# lelay.net
KiCad netlist of a schematic drawn in Altium Designer
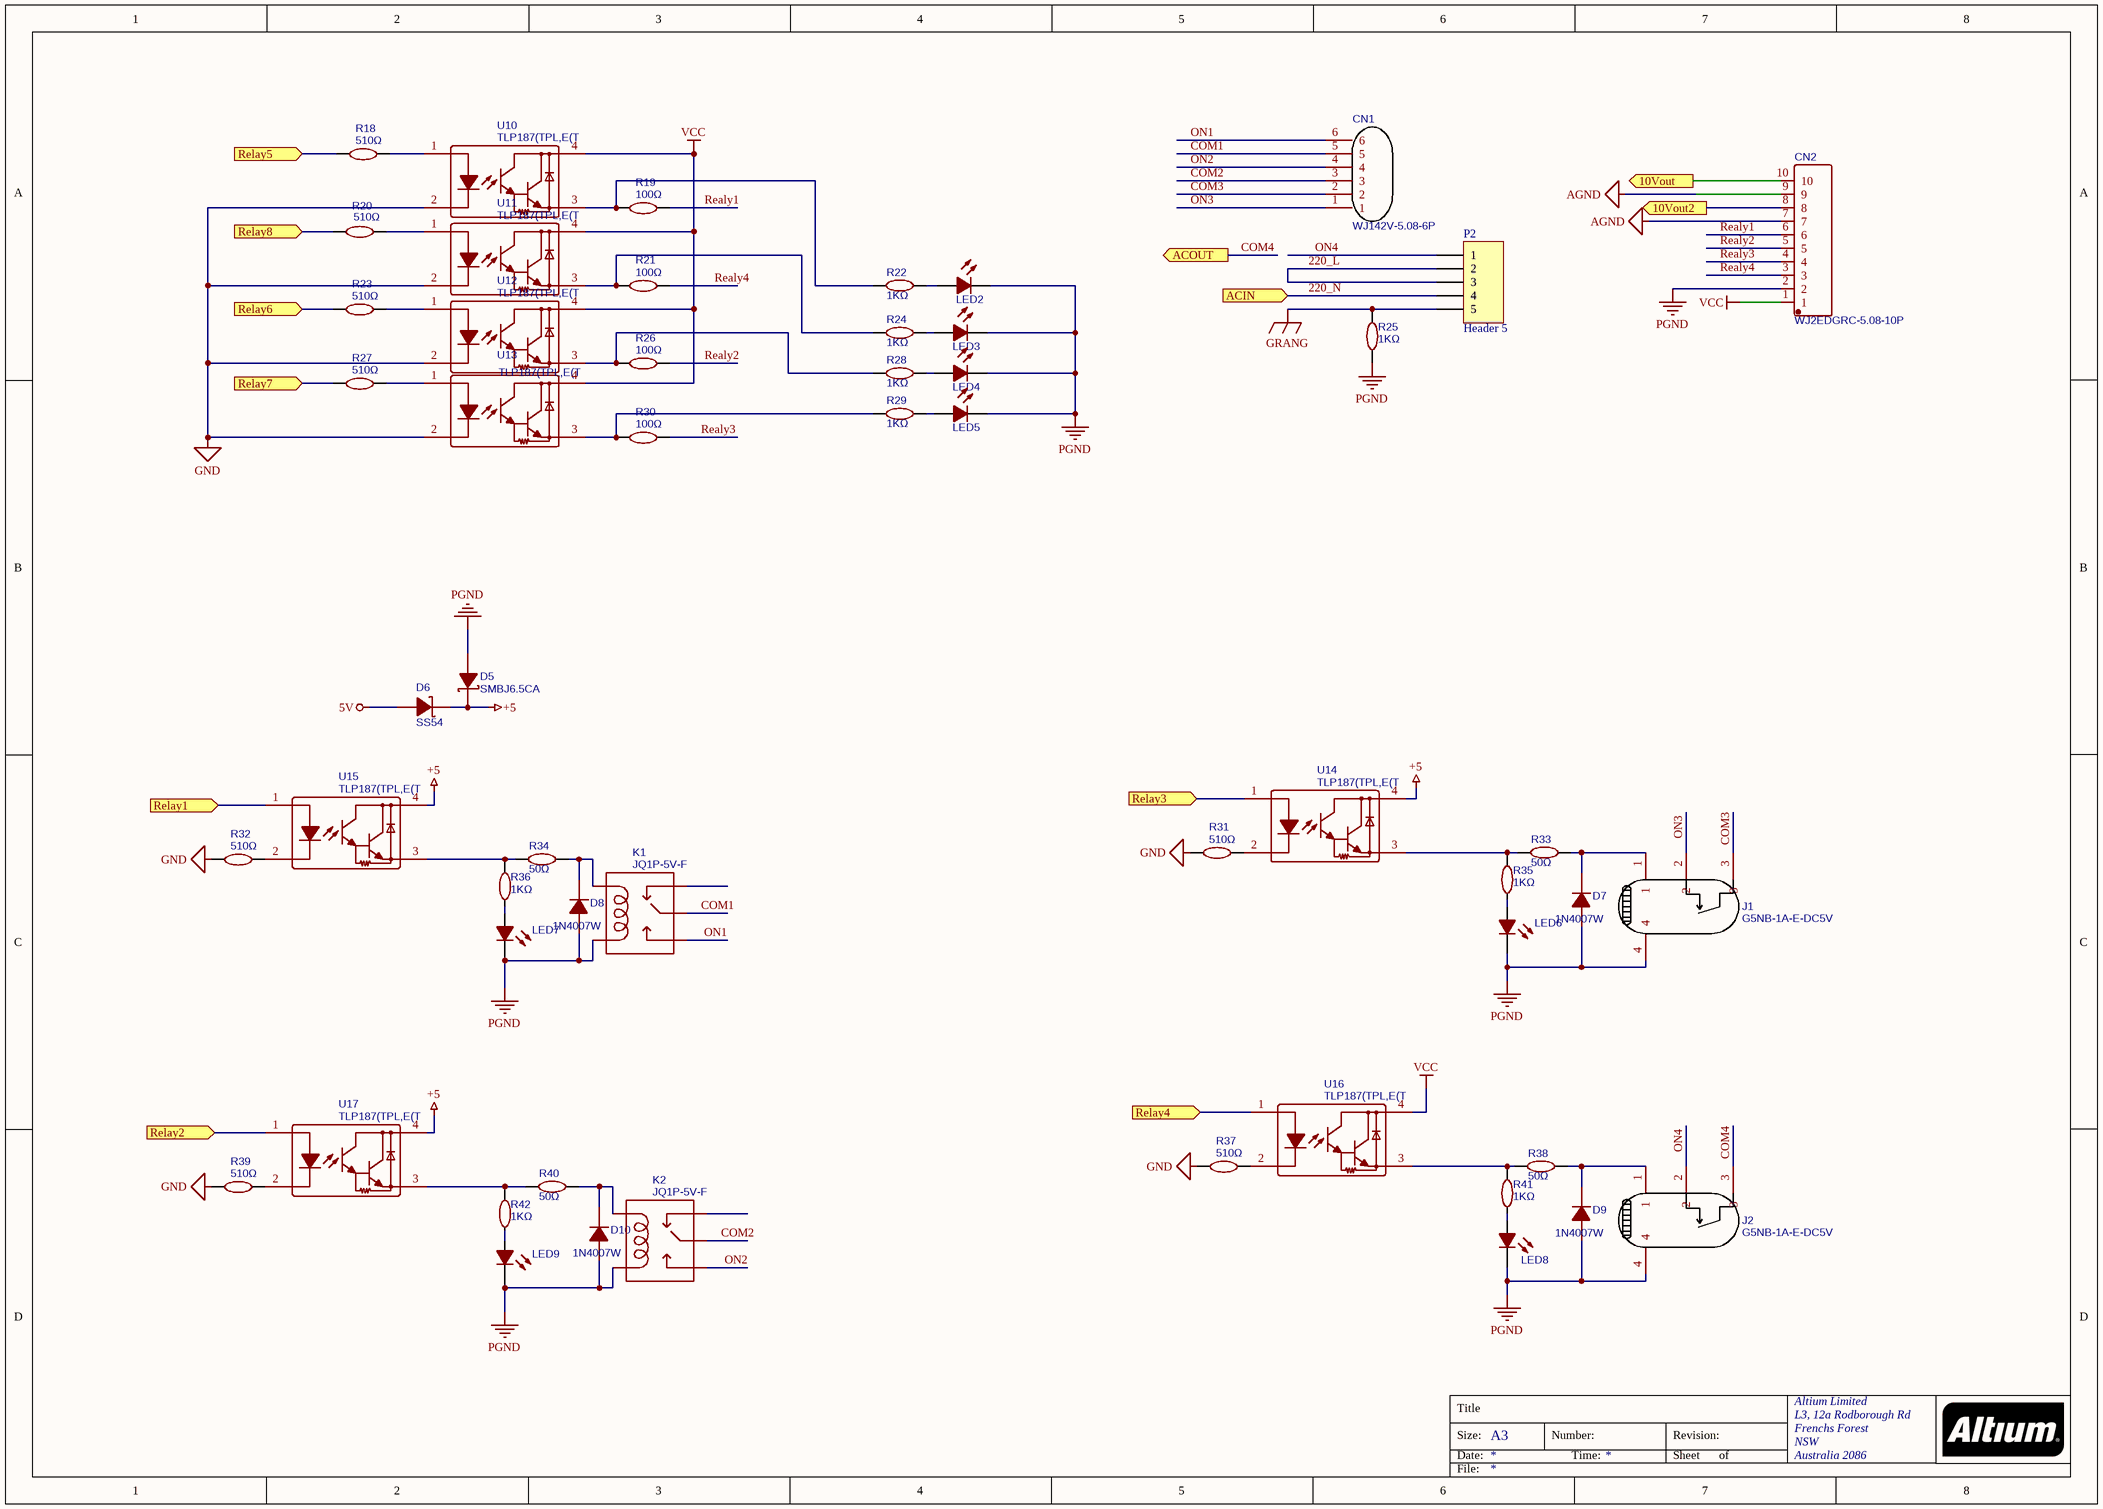
[diagram p0: lelay.SchDoc]

(export (version "E")
  (design (tool "Eeschema 10.0.6"))
  (components
    (comp (ref "CN1")
      (value "WJ142V-5.08-6P")
      (footprint "5.08_6P")
      (libsource (lib "altium-import") (part "root_1_mirrored__"))
    )
    (comp (ref "CN2")
      (value "WJ2EDGRC-5.08-10P")
      (footprint "WJ2EDGRC-5.08-10P")
      (libsource (lib "altium-import") (part "root_2_mirrored__"))
    )
    (comp (ref "D5")
      (value "SMBJ6.5CA")
      (footprint "SMB(DO-214AA)")
      (libsource (lib "altium-import") (part "root_1__"))
    )
    (comp (ref "D6") (value "SS54") (footprint "SMA(DO-214AC)") (libsource (lib "") (part "root_0___4")))
    (comp (ref "D7")
      (value "1N4007W")
      (footprint "SOD-123FL")
      (libsource (lib "altium-import") (part "root_3__"))
    )
    (comp (ref "D8")
      (value "1N4007W")
      (footprint "SOD-123FL")
      (libsource (lib "altium-import") (part "root_3__"))
    )
    (comp (ref "D9")
      (value "1N4007W")
      (footprint "SOD-123FL")
      (libsource (lib "altium-import") (part "root_3__"))
    )
    (comp (ref "D10")
      (value "1N4007W")
      (footprint "SOD-123FL")
      (libsource (lib "altium-import") (part "root_3__"))
    )
    (comp (ref "J1")
      (value "G5NB-1A-E-DC5V")
      (footprint "G5NB-1A-E-DC5V")
      (libsource (lib "") (part "root_0___6"))
    )
    (comp (ref "J2") (value "G5NB-1A-E-DC5V") (footprint "继电器") (libsource (lib "") (part "root_0___6")))
    (comp (ref "K1") (value "JQ1P-5V-F") (footprint "JQ1P-5V-F") (libsource (lib "") (part "root_0___5")))
    (comp (ref "K2") (value "JQ1P-5V-F") (footprint "JQ1P-5V-F") (libsource (lib "") (part "root_0___5")))
    (comp (ref "LED2")
      (value "19-217/GHC-YR1S2/3T")
      (footprint "LED-0603")
      (libsource (lib "altium-import") (part "root_0__"))
    )
    (comp (ref "LED3")
      (value "19-217/GHC-YR1S2/3T")
      (footprint "LED-0603")
      (libsource (lib "altium-import") (part "root_0__"))
    )
    (comp (ref "LED4")
      (value "19-217/GHC-YR1S2/3T")
      (footprint "LED-0603")
      (libsource (lib "altium-import") (part "root_0__"))
    )
    (comp (ref "LED5")
      (value "19-217/GHC-YR1S2/3T")
      (footprint "LED-0603")
      (libsource (lib "altium-import") (part "root_0__"))
    )
    (comp (ref "LED6")
      (value "19-217/GHC-YR1S2/3T")
      (footprint "LED-0603")
      (libsource (lib "") (part "root_3___2"))
    )
    (comp (ref "LED7")
      (value "19-217/GHC-YR1S2/3T")
      (footprint "LED-0603")
      (libsource (lib "") (part "root_3___2"))
    )
    (comp (ref "LED8")
      (value "19-217/GHC-YR1S2/3T")
      (footprint "LED-0603")
      (libsource (lib "") (part "root_3___2"))
    )
    (comp (ref "LED9")
      (value "19-217/GHC-YR1S2/3T")
      (footprint "LED-0603")
      (libsource (lib "") (part "root_3___2"))
    )
    (comp (ref "P2")
      (value "Header 5")
      (footprint "5p-7.62")
      (description "Header, 5-Pin")
      (fields (field (name "PUBLISHER") "Altium Limited"))
      (libsource (lib "Miscellaneous Connectors") (part "Header 5"))
    )
    (comp (ref "R18")
      (value "510Ω")
      (footprint "0603-res")
      (fields (field (name "BOM_MANUFACTURER PART") "0603WAF5100T5E"))
      (libsource (lib "") (part "root_0___3"))
    )
    (comp (ref "R19")
      (value "100Ω")
      (footprint "0603-res")
      (fields (field (name "BOM_MANUFACTURER PART") "0603WAF5100T5E"))
      (libsource (lib "") (part "root_0___3"))
    )
    (comp (ref "R20")
      (value "510Ω")
      (footprint "0603-res")
      (fields (field (name "BOM_MANUFACTURER PART") "0603WAF5100T5E"))
      (libsource (lib "") (part "root_0___3"))
    )
    (comp (ref "R21")
      (value "100Ω")
      (footprint "0603-res")
      (fields (field (name "BOM_MANUFACTURER PART") "0603WAF5100T5E"))
      (libsource (lib "") (part "root_0___3"))
    )
    (comp (ref "R22")
      (value "1KΩ")
      (footprint "0603-res")
      (fields (field (name "BOM_MANUFACTURER PART") "0603WAF1001T5E"))
      (libsource (lib "") (part "root_0___1"))
    )
    (comp (ref "R23")
      (value "510Ω")
      (footprint "0603-res")
      (fields (field (name "BOM_MANUFACTURER PART") "0603WAF5100T5E"))
      (libsource (lib "") (part "root_0___3"))
    )
    (comp (ref "R24")
      (value "1KΩ")
      (footprint "0603-res")
      (fields (field (name "BOM_MANUFACTURER PART") "0603WAF1001T5E"))
      (libsource (lib "") (part "root_0___1"))
    )
    (comp (ref "R25")
      (value "1KΩ")
      (footprint "0603-res")
      (fields (field (name "BOM_MANUFACTURER PART") "0603WAF1001T5E"))
      (libsource (lib "") (part "root_1___1"))
    )
    (comp (ref "R26")
      (value "100Ω")
      (footprint "0603-res")
      (fields (field (name "BOM_MANUFACTURER PART") "0603WAF5100T5E"))
      (libsource (lib "") (part "root_0___3"))
    )
    (comp (ref "R27")
      (value "510Ω")
      (footprint "0603-res")
      (fields (field (name "BOM_MANUFACTURER PART") "0603WAF5100T5E"))
      (libsource (lib "") (part "root_0___3"))
    )
    (comp (ref "R28")
      (value "1KΩ")
      (footprint "0603-res")
      (fields (field (name "BOM_MANUFACTURER PART") "0603WAF1001T5E"))
      (libsource (lib "") (part "root_0___1"))
    )
    (comp (ref "R29")
      (value "1KΩ")
      (footprint "0603-res")
      (fields (field (name "BOM_MANUFACTURER PART") "0603WAF1001T5E"))
      (libsource (lib "") (part "root_0___1"))
    )
    (comp (ref "R30")
      (value "100Ω")
      (footprint "0603-res")
      (fields (field (name "BOM_MANUFACTURER PART") "0603WAF5100T5E"))
      (libsource (lib "") (part "root_0___3"))
    )
    (comp (ref "R31")
      (value "510Ω")
      (footprint "0603-res")
      (fields (field (name "BOM_MANUFACTURER PART") "0603WAF5100T5E"))
      (libsource (lib "") (part "root_0___3"))
    )
    (comp (ref "R32")
      (value "510Ω")
      (footprint "0603-res")
      (fields (field (name "BOM_MANUFACTURER PART") "0603WAF5100T5E"))
      (libsource (lib "") (part "root_0___3"))
    )
    (comp (ref "R33")
      (value "50Ω")
      (footprint "0603-res")
      (fields (field (name "BOM_MANUFACTURER PART") "0603WAF1001T5E"))
      (libsource (lib "") (part "root_0___1"))
    )
    (comp (ref "R34")
      (value "50Ω")
      (footprint "0603-res")
      (fields (field (name "BOM_MANUFACTURER PART") "0603WAF1001T5E"))
      (libsource (lib "") (part "root_0___1"))
    )
    (comp (ref "R35")
      (value "1KΩ")
      (footprint "0603-res")
      (fields (field (name "BOM_MANUFACTURER PART") "0603WAF1001T5E"))
      (libsource (lib "") (part "root_3___1"))
    )
    (comp (ref "R36")
      (value "1KΩ")
      (footprint "0603-res")
      (fields (field (name "BOM_MANUFACTURER PART") "0603WAF1001T5E"))
      (libsource (lib "") (part "root_3___1"))
    )
    (comp (ref "R37")
      (value "510Ω")
      (footprint "0603-res")
      (fields (field (name "BOM_MANUFACTURER PART") "0603WAF5100T5E"))
      (libsource (lib "") (part "root_0___3"))
    )
    (comp (ref "R38")
      (value "50Ω")
      (footprint "0603-res")
      (fields (field (name "BOM_MANUFACTURER PART") "0603WAF1001T5E"))
      (libsource (lib "") (part "root_0___1"))
    )
    (comp (ref "R39")
      (value "510Ω")
      (footprint "0603-res")
      (fields (field (name "BOM_MANUFACTURER PART") "0603WAF5100T5E"))
      (libsource (lib "") (part "root_0___3"))
    )
    (comp (ref "R40")
      (value "50Ω")
      (footprint "0603-res")
      (fields (field (name "BOM_MANUFACTURER PART") "0603WAF1001T5E"))
      (libsource (lib "") (part "root_0___1"))
    )
    (comp (ref "R41")
      (value "1KΩ")
      (footprint "0603-res")
      (fields (field (name "BOM_MANUFACTURER PART") "0603WAF1001T5E"))
      (libsource (lib "") (part "root_3___1"))
    )
    (comp (ref "R42")
      (value "1KΩ")
      (footprint "0603-res")
      (fields (field (name "BOM_MANUFACTURER PART") "0603WAF1001T5E"))
      (libsource (lib "") (part "root_3___1"))
    )
    (comp (ref "U10") (value "TLP187(TPL,E(T") (footprint "TLP187") (libsource (lib "") (part "root_0___2")))
    (comp (ref "U11") (value "TLP187(TPL,E(T") (footprint "TLP187") (libsource (lib "") (part "root_0___2")))
    (comp (ref "U12") (value "TLP187(TPL,E(T") (footprint "TLP187") (libsource (lib "") (part "root_0___2")))
    (comp (ref "U13") (value "TLP187(TPL,E(T") (footprint "TLP187") (libsource (lib "") (part "root_0___2")))
    (comp (ref "U14") (value "TLP187(TPL,E(T") (footprint "TLP187") (libsource (lib "") (part "root_0___2")))
    (comp (ref "U15") (value "TLP187(TPL,E(T") (footprint "TLP187") (libsource (lib "") (part "root_0___2")))
    (comp (ref "U16") (value "TLP187(TPL,E(T") (footprint "TLP187") (libsource (lib "") (part "root_0___2")))
    (comp (ref "U17") (value "TLP187(TPL,E(T") (footprint "TLP187") (libsource (lib "") (part "root_0___2")))
  )
  (nets
    (net (code "1") (name "+5") (class "Default")
      (node (ref "D5") (pin "2") (pinfunction "2_2") (pintype "passive"))
      (node (ref "D6") (pin "2") (pinfunction "K_2") (pintype "passive"))
      (node (ref "U14") (pin "4") (pinfunction "4_4") (pintype "passive"))
      (node (ref "U15") (pin "4") (pinfunction "4_4") (pintype "passive"))
      (node (ref "U17") (pin "4") (pinfunction "4_4") (pintype "passive"))
    )
    (net (code "2") (name "/10Vout") (class "Default")
      (node (ref "CN2") (pin "10") (pinfunction "10_10") (pintype "passive"))
    )
    (net (code "3") (name "/10Vout2") (class "Default")
      (node (ref "CN2") (pin "8") (pinfunction "8_8") (pintype "passive"))
    )
    (net (code "4") (name "/220_L") (class "Default")
      (node (ref "P2") (pin "2") (pinfunction "2_2") (pintype "passive"))
      (node (ref "P2") (pin "3") (pinfunction "3_3") (pintype "passive"))
    )
    (net (code "5") (name "/220_N") (class "Default")
      (node (ref "P2") (pin "4") (pinfunction "4_4") (pintype "passive"))
    )
    (net (code "6") (name "/COM1") (class "Default")
      (node (ref "CN1") (pin "5") (pinfunction "5_5") (pintype "passive"))
      (node (ref "K1") (pin "4") (pinfunction "4_4") (pintype "passive"))
    )
    (net (code "7") (name "/COM2") (class "Default")
      (node (ref "CN1") (pin "3") (pinfunction "3_3") (pintype "passive"))
      (node (ref "K2") (pin "4") (pinfunction "4_4") (pintype "passive"))
    )
    (net (code "8") (name "/COM3") (class "Default")
      (node (ref "CN1") (pin "2") (pinfunction "2_2") (pintype "passive"))
      (node (ref "J1") (pin "3") (pinfunction "3_3") (pintype "passive"))
    )
    (net (code "9") (name "/COM4") (class "Default")
      (node (ref "J2") (pin "3") (pinfunction "3_3") (pintype "passive"))
    )
    (net (code "10") (name "/ON1") (class "Default")
      (node (ref "CN1") (pin "6") (pinfunction "6_6") (pintype "passive"))
      (node (ref "K1") (pin "5") (pinfunction "5_5") (pintype "passive"))
    )
    (net (code "11") (name "/ON2") (class "Default")
      (node (ref "CN1") (pin "4") (pinfunction "4_4") (pintype "passive"))
      (node (ref "K2") (pin "5") (pinfunction "5_5") (pintype "passive"))
    )
    (net (code "12") (name "/ON3") (class "Default")
      (node (ref "CN1") (pin "1") (pinfunction "1_1") (pintype "passive"))
      (node (ref "J1") (pin "2") (pinfunction "2_2") (pintype "passive"))
    )
    (net (code "13") (name "/ON4") (class "Default")
      (node (ref "J2") (pin "2") (pinfunction "2_2") (pintype "passive"))
      (node (ref "P2") (pin "1") (pinfunction "1_1") (pintype "passive"))
    )
    (net (code "14") (name "/Realy1") (class "Default")
      (node (ref "CN2") (pin "6") (pinfunction "6_6") (pintype "passive"))
      (node (ref "R19") (pin "2") (pinfunction "2_2") (pintype "passive"))
    )
    (net (code "15") (name "/Realy2") (class "Default")
      (node (ref "CN2") (pin "5") (pinfunction "5_5") (pintype "passive"))
      (node (ref "R26") (pin "2") (pinfunction "2_2") (pintype "passive"))
    )
    (net (code "16") (name "/Realy3") (class "Default")
      (node (ref "CN2") (pin "4") (pinfunction "4_4") (pintype "passive"))
      (node (ref "R30") (pin "2") (pinfunction "2_2") (pintype "passive"))
    )
    (net (code "17") (name "/Realy4") (class "Default")
      (node (ref "CN2") (pin "3") (pinfunction "3_3") (pintype "passive"))
      (node (ref "R21") (pin "2") (pinfunction "2_2") (pintype "passive"))
    )
    (net (code "18") (name "/Relay1") (class "Default")
      (node (ref "U15") (pin "1") (pinfunction "1_1") (pintype "passive"))
    )
    (net (code "19") (name "/Relay2") (class "Default")
      (node (ref "U17") (pin "1") (pinfunction "1_1") (pintype "passive"))
    )
    (net (code "20") (name "/Relay3") (class "Default")
      (node (ref "U14") (pin "1") (pinfunction "1_1") (pintype "passive"))
    )
    (net (code "21") (name "/Relay4") (class "Default")
      (node (ref "U16") (pin "1") (pinfunction "1_1") (pintype "passive"))
    )
    (net (code "22") (name "/Relay5") (class "Default")
      (node (ref "R18") (pin "1") (pinfunction "1_1") (pintype "passive"))
    )
    (net (code "23") (name "/Relay6") (class "Default")
      (node (ref "R23") (pin "1") (pinfunction "1_1") (pintype "passive"))
    )
    (net (code "24") (name "/Relay7") (class "Default")
      (node (ref "R27") (pin "1") (pinfunction "1_1") (pintype "passive"))
    )
    (net (code "25") (name "/Relay8") (class "Default")
      (node (ref "R20") (pin "1") (pinfunction "1_1") (pintype "passive"))
    )
    (net (code "26") (name "5V") (class "Default")
      (node (ref "D6") (pin "1") (pinfunction "A_1") (pintype "passive"))
    )
    (net (code "27") (name "AGND") (class "Default")
      (node (ref "CN2") (pin "7") (pinfunction "7_7") (pintype "passive"))
      (node (ref "CN2") (pin "9") (pinfunction "9_9") (pintype "passive"))
    )
    (net (code "28") (name "GND") (class "Default")
      (node (ref "R31") (pin "1") (pinfunction "1_1") (pintype "passive"))
      (node (ref "R32") (pin "1") (pinfunction "1_1") (pintype "passive"))
      (node (ref "R37") (pin "1") (pinfunction "1_1") (pintype "passive"))
      (node (ref "R39") (pin "1") (pinfunction "1_1") (pintype "passive"))
      (node (ref "U10") (pin "2") (pinfunction "2_2") (pintype "passive"))
      (node (ref "U11") (pin "2") (pinfunction "2_2") (pintype "passive"))
      (node (ref "U12") (pin "2") (pinfunction "2_2") (pintype "passive"))
      (node (ref "U13") (pin "2") (pinfunction "2_2") (pintype "passive"))
    )
    (net (code "29") (name "GRANG") (class "Default")
      (node (ref "P2") (pin "5") (pinfunction "5_5") (pintype "passive"))
      (node (ref "R25") (pin "2") (pinfunction "2_2") (pintype "passive"))
    )
    (net (code "30") (name "Net-(D7-K)") (class "Default")
      (node (ref "D7") (pin "1") (pinfunction "K_1") (pintype "passive"))
      (node (ref "J1") (pin "1") (pinfunction "1_1") (pintype "passive"))
      (node (ref "R33") (pin "2") (pinfunction "2_2") (pintype "passive"))
    )
    (net (code "31") (name "Net-(D8-K)") (class "Default")
      (node (ref "D8") (pin "1") (pinfunction "K_1") (pintype "passive"))
      (node (ref "K1") (pin "2") (pinfunction "2_2") (pintype "passive"))
      (node (ref "R34") (pin "2") (pinfunction "2_2") (pintype "passive"))
    )
    (net (code "32") (name "Net-(D9-K)") (class "Default")
      (node (ref "D9") (pin "1") (pinfunction "K_1") (pintype "passive"))
      (node (ref "J2") (pin "1") (pinfunction "1_1") (pintype "passive"))
      (node (ref "R38") (pin "2") (pinfunction "2_2") (pintype "passive"))
    )
    (net (code "33") (name "Net-(D10-K)") (class "Default")
      (node (ref "D10") (pin "1") (pinfunction "K_1") (pintype "passive"))
      (node (ref "K2") (pin "2") (pinfunction "2_2") (pintype "passive"))
      (node (ref "R40") (pin "2") (pinfunction "2_2") (pintype "passive"))
    )
    (net (code "34") (name "Net-(LED2-A)") (class "Default")
      (node (ref "LED2") (pin "1") (pinfunction "A_1") (pintype "passive"))
      (node (ref "R22") (pin "2") (pinfunction "2_2") (pintype "passive"))
    )
    (net (code "35") (name "Net-(LED3-A)") (class "Default")
      (node (ref "LED3") (pin "1") (pinfunction "A_1") (pintype "passive"))
      (node (ref "R24") (pin "2") (pinfunction "2_2") (pintype "passive"))
    )
    (net (code "36") (name "Net-(LED4-A)") (class "Default")
      (node (ref "LED4") (pin "1") (pinfunction "A_1") (pintype "passive"))
      (node (ref "R28") (pin "2") (pinfunction "2_2") (pintype "passive"))
    )
    (net (code "37") (name "Net-(LED5-A)") (class "Default")
      (node (ref "LED5") (pin "1") (pinfunction "A_1") (pintype "passive"))
      (node (ref "R29") (pin "2") (pinfunction "2_2") (pintype "passive"))
    )
    (net (code "38") (name "Net-(LED6-A)") (class "Default")
      (node (ref "LED6") (pin "1") (pinfunction "A_1") (pintype "passive"))
      (node (ref "R35") (pin "2") (pinfunction "2_2") (pintype "passive"))
    )
    (net (code "39") (name "Net-(LED7-A)") (class "Default")
      (node (ref "LED7") (pin "1") (pinfunction "A_1") (pintype "passive"))
      (node (ref "R36") (pin "2") (pinfunction "2_2") (pintype "passive"))
    )
    (net (code "40") (name "Net-(LED8-A)") (class "Default")
      (node (ref "LED8") (pin "1") (pinfunction "A_1") (pintype "passive"))
      (node (ref "R41") (pin "2") (pinfunction "2_2") (pintype "passive"))
    )
    (net (code "41") (name "Net-(LED9-A)") (class "Default")
      (node (ref "LED9") (pin "1") (pinfunction "A_1") (pintype "passive"))
      (node (ref "R42") (pin "2") (pinfunction "2_2") (pintype "passive"))
    )
    (net (code "42") (name "Net-(R18-Pad2)") (class "Default")
      (node (ref "R18") (pin "2") (pinfunction "2_2") (pintype "passive"))
      (node (ref "U10") (pin "1") (pinfunction "1_1") (pintype "passive"))
    )
    (net (code "43") (name "Net-(R19-Pad1)") (class "Default")
      (node (ref "R19") (pin "1") (pinfunction "1_1") (pintype "passive"))
      (node (ref "R22") (pin "1") (pinfunction "1_1") (pintype "passive"))
      (node (ref "U10") (pin "3") (pinfunction "3_3") (pintype "passive"))
    )
    (net (code "44") (name "Net-(R20-Pad2)") (class "Default")
      (node (ref "R20") (pin "2") (pinfunction "2_2") (pintype "passive"))
      (node (ref "U11") (pin "1") (pinfunction "1_1") (pintype "passive"))
    )
    (net (code "45") (name "Net-(R21-Pad1)") (class "Default")
      (node (ref "R21") (pin "1") (pinfunction "1_1") (pintype "passive"))
      (node (ref "R24") (pin "1") (pinfunction "1_1") (pintype "passive"))
      (node (ref "U11") (pin "3") (pinfunction "3_3") (pintype "passive"))
    )
    (net (code "46") (name "Net-(R23-Pad2)") (class "Default")
      (node (ref "R23") (pin "2") (pinfunction "2_2") (pintype "passive"))
      (node (ref "U12") (pin "1") (pinfunction "1_1") (pintype "passive"))
    )
    (net (code "47") (name "Net-(R26-Pad1)") (class "Default")
      (node (ref "R26") (pin "1") (pinfunction "1_1") (pintype "passive"))
      (node (ref "R28") (pin "1") (pinfunction "1_1") (pintype "passive"))
      (node (ref "U12") (pin "3") (pinfunction "3_3") (pintype "passive"))
    )
    (net (code "48") (name "Net-(R27-Pad2)") (class "Default")
      (node (ref "R27") (pin "2") (pinfunction "2_2") (pintype "passive"))
      (node (ref "U13") (pin "1") (pinfunction "1_1") (pintype "passive"))
    )
    (net (code "49") (name "Net-(R29-Pad1)") (class "Default")
      (node (ref "R29") (pin "1") (pinfunction "1_1") (pintype "passive"))
      (node (ref "R30") (pin "1") (pinfunction "1_1") (pintype "passive"))
      (node (ref "U13") (pin "3") (pinfunction "3_3") (pintype "passive"))
    )
    (net (code "50") (name "Net-(R31-Pad2)") (class "Default")
      (node (ref "R31") (pin "2") (pinfunction "2_2") (pintype "passive"))
      (node (ref "U14") (pin "2") (pinfunction "2_2") (pintype "passive"))
    )
    (net (code "51") (name "Net-(R32-Pad2)") (class "Default")
      (node (ref "R32") (pin "2") (pinfunction "2_2") (pintype "passive"))
      (node (ref "U15") (pin "2") (pinfunction "2_2") (pintype "passive"))
    )
    (net (code "52") (name "Net-(R33-Pad1)") (class "Default")
      (node (ref "R33") (pin "1") (pinfunction "1_1") (pintype "passive"))
      (node (ref "R35") (pin "1") (pinfunction "1_1") (pintype "passive"))
      (node (ref "U14") (pin "3") (pinfunction "3_3") (pintype "passive"))
    )
    (net (code "53") (name "Net-(R34-Pad1)") (class "Default")
      (node (ref "R34") (pin "1") (pinfunction "1_1") (pintype "passive"))
      (node (ref "R36") (pin "1") (pinfunction "1_1") (pintype "passive"))
      (node (ref "U15") (pin "3") (pinfunction "3_3") (pintype "passive"))
    )
    (net (code "54") (name "Net-(R37-Pad2)") (class "Default")
      (node (ref "R37") (pin "2") (pinfunction "2_2") (pintype "passive"))
      (node (ref "U16") (pin "2") (pinfunction "2_2") (pintype "passive"))
    )
    (net (code "55") (name "Net-(R38-Pad1)") (class "Default")
      (node (ref "R38") (pin "1") (pinfunction "1_1") (pintype "passive"))
      (node (ref "R41") (pin "1") (pinfunction "1_1") (pintype "passive"))
      (node (ref "U16") (pin "3") (pinfunction "3_3") (pintype "passive"))
    )
    (net (code "56") (name "Net-(R39-Pad2)") (class "Default")
      (node (ref "R39") (pin "2") (pinfunction "2_2") (pintype "passive"))
      (node (ref "U17") (pin "2") (pinfunction "2_2") (pintype "passive"))
    )
    (net (code "57") (name "Net-(R40-Pad1)") (class "Default")
      (node (ref "R40") (pin "1") (pinfunction "1_1") (pintype "passive"))
      (node (ref "R42") (pin "1") (pinfunction "1_1") (pintype "passive"))
      (node (ref "U17") (pin "3") (pinfunction "3_3") (pintype "passive"))
    )
    (net (code "58") (name "PGND") (class "Default")
      (node (ref "CN2") (pin "2") (pinfunction "2_2") (pintype "passive"))
      (node (ref "D10") (pin "2") (pinfunction "A_2") (pintype "passive"))
      (node (ref "D5") (pin "1") (pinfunction "1_1") (pintype "passive"))
      (node (ref "D7") (pin "2") (pinfunction "A_2") (pintype "passive"))
      (node (ref "D8") (pin "2") (pinfunction "A_2") (pintype "passive"))
      (node (ref "D9") (pin "2") (pinfunction "A_2") (pintype "passive"))
      (node (ref "J1") (pin "4") (pinfunction "4_4") (pintype "passive"))
      (node (ref "J2") (pin "4") (pinfunction "4_4") (pintype "passive"))
      (node (ref "K1") (pin "1") (pinfunction "1_1") (pintype "passive"))
      (node (ref "K2") (pin "1") (pinfunction "1_1") (pintype "passive"))
      (node (ref "LED2") (pin "2") (pinfunction "C_2") (pintype "passive"))
      (node (ref "LED3") (pin "2") (pinfunction "C_2") (pintype "passive"))
      (node (ref "LED4") (pin "2") (pinfunction "C_2") (pintype "passive"))
      (node (ref "LED5") (pin "2") (pinfunction "C_2") (pintype "passive"))
      (node (ref "LED6") (pin "2") (pinfunction "C_2") (pintype "passive"))
      (node (ref "LED7") (pin "2") (pinfunction "C_2") (pintype "passive"))
      (node (ref "LED8") (pin "2") (pinfunction "C_2") (pintype "passive"))
      (node (ref "LED9") (pin "2") (pinfunction "C_2") (pintype "passive"))
      (node (ref "R25") (pin "1") (pinfunction "1_1") (pintype "passive"))
    )
    (net (code "59") (name "VCC") (class "Default")
      (node (ref "CN2") (pin "1") (pinfunction "1_1") (pintype "passive"))
      (node (ref "U10") (pin "4") (pinfunction "4_4") (pintype "passive"))
      (node (ref "U11") (pin "4") (pinfunction "4_4") (pintype "passive"))
      (node (ref "U12") (pin "4") (pinfunction "4_4") (pintype "passive"))
      (node (ref "U13") (pin "4") (pinfunction "4_4") (pintype "passive"))
      (node (ref "U16") (pin "4") (pinfunction "4_4") (pintype "passive"))
    )
    (net (code "60") (name "unconnected-(K1-Pad3)") (class "Default")
      (node (ref "K1") (pin "3") (pinfunction "3_3") (pintype "passive"))
    )
    (net (code "61") (name "unconnected-(K2-Pad3)") (class "Default")
      (node (ref "K2") (pin "3") (pinfunction "3_3") (pintype "passive"))
    )
  )
)
